# Communication_and_peripherals.net
KiCad netlist of a schematic drawn in Altium Designer
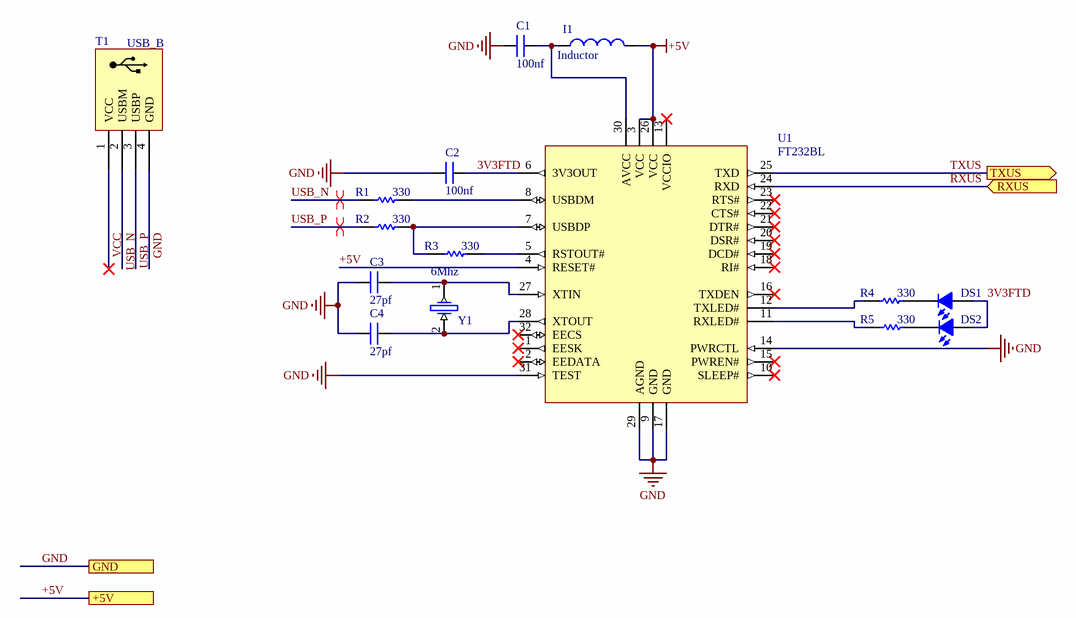
[diagram p0: Communication and peripherals.SchDoc]

(export (version "E")
  (design (tool "Eeschema 10.0.6"))
  (components
    (comp (ref "C1")
      (value "100nf")
      (footprint "Cap0805")
      (description "Surface mount Capacitor")
      (libsource (lib "PMLIB2020") (part "Cap"))
    )
    (comp (ref "C2")
      (value "100nf")
      (footprint "Cap0805")
      (description "Surface mount Capacitor")
      (libsource (lib "PMLIB2020") (part "Cap"))
    )
    (comp (ref "C3")
      (value "27pf")
      (footprint "Cap0805")
      (description "Surface mount Capacitor")
      (libsource (lib "PMLIB2020") (part "Cap"))
    )
    (comp (ref "C4")
      (value "27pf")
      (footprint "Cap0805")
      (description "Surface mount Capacitor")
      (libsource (lib "PMLIB2020") (part "Cap"))
    )
    (comp (ref "DS1") (value "LED") (footprint "Led0805") (libsource (lib "PMLIB2020") (part "LED")))
    (comp (ref "DS2") (value "LED") (footprint "Led0805") (libsource (lib "PMLIB2020") (part "LED")))
    (comp (ref "I1")
      (value "Inductor")
      (footprint "1206")
      (description "Indicator")
      (libsource (lib "PMLIB2020") (part "Inductor"))
    )
    (comp (ref "R1")
      (value "330")
      (footprint "R0805")
      (description "Resistor")
      (libsource (lib "PMLIB2020") (part "Resistor"))
    )
    (comp (ref "R2")
      (value "330")
      (footprint "R0805")
      (description "Resistor")
      (libsource (lib "PMLIB2020") (part "Resistor"))
    )
    (comp (ref "R3")
      (value "330")
      (footprint "R0805")
      (description "Resistor")
      (libsource (lib "PMLIB2020") (part "Resistor"))
    )
    (comp (ref "R4")
      (value "330")
      (footprint "R0805")
      (description "Resistor")
      (libsource (lib "PMLIB2020") (part "Resistor"))
    )
    (comp (ref "R5")
      (value "330")
      (footprint "R0805")
      (description "Resistor")
      (libsource (lib "PMLIB2020") (part "Resistor"))
    )
    (comp (ref "T1")
      (value "USB_B")
      (footprint "USB_Dip_R")
      (description "USB B Connector")
      (libsource (lib "PMLIB2020") (part "USB_B"))
    )
    (comp (ref "U1")
      (value "FT232BL")
      (footprint "LQFP-32_L")
      (description "USB UART Asynchronous Serial Data Transfer Chip, LQFP-32, Pb-Free")
      (libsource (lib "FTDI Communication") (part "FT232BL"))
    )
    (comp (ref "Y1")
      (value "6Mhz")
      (footprint "CrystallB")
      (description "Crystal")
      (libsource (lib "PMLIB2020") (part "Crystal"))
    )
  )
  (nets
    (net (code "1") (name "+5V") (class "Default")
      (node (ref "I1") (pin "2") (pinfunction "2_2") (pintype "passive"))
      (node (ref "U1") (pin "26") (pinfunction "VCC_26") (pintype "power_in"))
      (node (ref "U1") (pin "3") (pinfunction "VCC_3") (pintype "power_in"))
      (node (ref "U1") (pin "4") (pinfunction "RESET#_4") (pintype "input"))
    )
    (net (code "2") (name "/3V3FTD") (class "Default")
      (node (ref "C2") (pin "1") (pinfunction "1_1") (pintype "passive"))
      (node (ref "DS1") (pin "A") (pinfunction "A_A") (pintype "passive"))
      (node (ref "DS2") (pin "A") (pinfunction "A_A") (pintype "passive"))
      (node (ref "U1") (pin "6") (pinfunction "3V3OUT_6") (pintype "output"))
    )
    (net (code "3") (name "/RXUS") (class "Default")
      (node (ref "U1") (pin "24") (pinfunction "RXD_24") (pintype "input"))
    )
    (net (code "4") (name "/TXUS") (class "Default")
      (node (ref "U1") (pin "25") (pinfunction "TXD_25") (pintype "output"))
    )
    (net (code "5") (name "/USB_N") (class "Default")
      (node (ref "R1") (pin "1") (pinfunction "1_1") (pintype "passive"))
      (node (ref "T1") (pin "2") (pinfunction "USBM_2") (pintype "passive"))
    )
    (net (code "6") (name "/USB_P") (class "Default")
      (node (ref "R2") (pin "1") (pinfunction "1_1") (pintype "passive"))
      (node (ref "T1") (pin "3") (pinfunction "USBP_3") (pintype "passive"))
    )
    (net (code "7") (name "/VCC") (class "Default")
      (node (ref "T1") (pin "1") (pinfunction "VCC_1") (pintype "passive+no_connect"))
    )
    (net (code "8") (name "GND") (class "Default")
      (node (ref "C1") (pin "2") (pinfunction "2_2") (pintype "passive"))
      (node (ref "C2") (pin "2") (pinfunction "2_2") (pintype "passive"))
      (node (ref "C3") (pin "1") (pinfunction "1_1") (pintype "passive"))
      (node (ref "C4") (pin "1") (pinfunction "1_1") (pintype "passive"))
      (node (ref "T1") (pin "4") (pinfunction "GND_4") (pintype "passive"))
      (node (ref "U1") (pin "14") (pinfunction "PWRCTL_14") (pintype "input"))
      (node (ref "U1") (pin "17") (pinfunction "GND_17") (pintype "power_in"))
      (node (ref "U1") (pin "29") (pinfunction "AGND_29") (pintype "power_in"))
      (node (ref "U1") (pin "31") (pinfunction "TEST_31") (pintype "input"))
      (node (ref "U1") (pin "9") (pinfunction "GND_9") (pintype "power_in"))
    )
    (net (code "9") (name "Net-(DS1-PadK)") (class "Default")
      (node (ref "DS1") (pin "K") (pinfunction "K_K") (pintype "passive"))
      (node (ref "R4") (pin "2") (pinfunction "2_2") (pintype "passive"))
    )
    (net (code "10") (name "Net-(DS2-PadK)") (class "Default")
      (node (ref "DS2") (pin "K") (pinfunction "K_K") (pintype "passive"))
      (node (ref "R5") (pin "2") (pinfunction "2_2") (pintype "passive"))
    )
    (net (code "11") (name "Net-(U1-AVCC)") (class "Default")
      (node (ref "C1") (pin "1") (pinfunction "1_1") (pintype "passive"))
      (node (ref "I1") (pin "1") (pinfunction "1_1") (pintype "passive"))
      (node (ref "U1") (pin "30") (pinfunction "AVCC_30") (pintype "power_in"))
    )
    (net (code "12") (name "Net-(U1-RSTOUT#)") (class "Default")
      (node (ref "R3") (pin "2") (pinfunction "2_2") (pintype "passive"))
      (node (ref "U1") (pin "5") (pinfunction "RSTOUT#_5") (pintype "output"))
    )
    (net (code "13") (name "Net-(U1-RXLED#)") (class "Default")
      (node (ref "R5") (pin "1") (pinfunction "1_1") (pintype "passive"))
      (node (ref "U1") (pin "11") (pinfunction "RXLED#_11") (pintype "open_collector"))
    )
    (net (code "14") (name "Net-(U1-TXLED#)") (class "Default")
      (node (ref "R4") (pin "1") (pinfunction "1_1") (pintype "passive"))
      (node (ref "U1") (pin "12") (pinfunction "TXLED#_12") (pintype "open_collector"))
    )
    (net (code "15") (name "Net-(U1-USBDM)") (class "Default")
      (node (ref "R1") (pin "2") (pinfunction "2_2") (pintype "passive"))
      (node (ref "U1") (pin "8") (pinfunction "USBDM_8") (pintype "bidirectional"))
    )
    (net (code "16") (name "Net-(U1-USBDP)") (class "Default")
      (node (ref "R2") (pin "2") (pinfunction "2_2") (pintype "passive"))
      (node (ref "R3") (pin "1") (pinfunction "1_1") (pintype "passive"))
      (node (ref "U1") (pin "7") (pinfunction "USBDP_7") (pintype "bidirectional"))
    )
    (net (code "17") (name "Net-(U1-XTIN)") (class "Default")
      (node (ref "C3") (pin "2") (pinfunction "2_2") (pintype "passive"))
      (node (ref "U1") (pin "27") (pinfunction "XTIN_27") (pintype "input"))
      (node (ref "Y1") (pin "1") (pinfunction "1_1") (pintype "output"))
    )
    (net (code "18") (name "Net-(U1-XTOUT)") (class "Default")
      (node (ref "C4") (pin "2") (pinfunction "2_2") (pintype "passive"))
      (node (ref "U1") (pin "28") (pinfunction "XTOUT_28") (pintype "output"))
      (node (ref "Y1") (pin "2") (pinfunction "2_2") (pintype "input"))
    )
    (net (code "19") (name "unconnected-(U1-CTS#-Pad22)") (class "Default")
      (node (ref "U1") (pin "22") (pinfunction "CTS#_22") (pintype "input+no_connect"))
    )
    (net (code "20") (name "unconnected-(U1-DCD#-Pad19)") (class "Default")
      (node (ref "U1") (pin "19") (pinfunction "DCD#_19") (pintype "input+no_connect"))
    )
    (net (code "21") (name "unconnected-(U1-DSR#-Pad20)") (class "Default")
      (node (ref "U1") (pin "20") (pinfunction "DSR#_20") (pintype "input+no_connect"))
    )
    (net (code "22") (name "unconnected-(U1-DTR#-Pad21)") (class "Default")
      (node (ref "U1") (pin "21") (pinfunction "DTR#_21") (pintype "output+no_connect"))
    )
    (net (code "23") (name "unconnected-(U1-EECS-Pad32)") (class "Default")
      (node (ref "U1") (pin "32") (pinfunction "EECS_32") (pintype "bidirectional+no_connect"))
    )
    (net (code "24") (name "unconnected-(U1-EEDATA-Pad2)") (class "Default")
      (node (ref "U1") (pin "2") (pinfunction "EEDATA_2") (pintype "bidirectional+no_connect"))
    )
    (net (code "25") (name "unconnected-(U1-EESK-Pad1)") (class "Default")
      (node (ref "U1") (pin "1") (pinfunction "EESK_1") (pintype "output+no_connect"))
    )
    (net (code "26") (name "unconnected-(U1-PWREN#-Pad15)") (class "Default")
      (node (ref "U1") (pin "15") (pinfunction "PWREN#_15") (pintype "output+no_connect"))
    )
    (net (code "27") (name "unconnected-(U1-RI#-Pad18)") (class "Default")
      (node (ref "U1") (pin "18") (pinfunction "RI#_18") (pintype "input+no_connect"))
    )
    (net (code "28") (name "unconnected-(U1-RTS#-Pad23)") (class "Default")
      (node (ref "U1") (pin "23") (pinfunction "RTS#_23") (pintype "output+no_connect"))
    )
    (net (code "29") (name "unconnected-(U1-SLEEP#-Pad10)") (class "Default")
      (node (ref "U1") (pin "10") (pinfunction "SLEEP#_10") (pintype "output+no_connect"))
    )
    (net (code "30") (name "unconnected-(U1-TXDEN-Pad16)") (class "Default")
      (node (ref "U1") (pin "16") (pinfunction "TXDEN_16") (pintype "output+no_connect"))
    )
    (net (code "31") (name "unconnected-(U1-VCCIO-Pad13)") (class "Default")
      (node (ref "U1") (pin "13") (pinfunction "VCCIO_13") (pintype "power_in+no_connect"))
    )
  )
)
